# STM32F108CBT6.net
KiCad netlist of a schematic drawn in Altium Designer
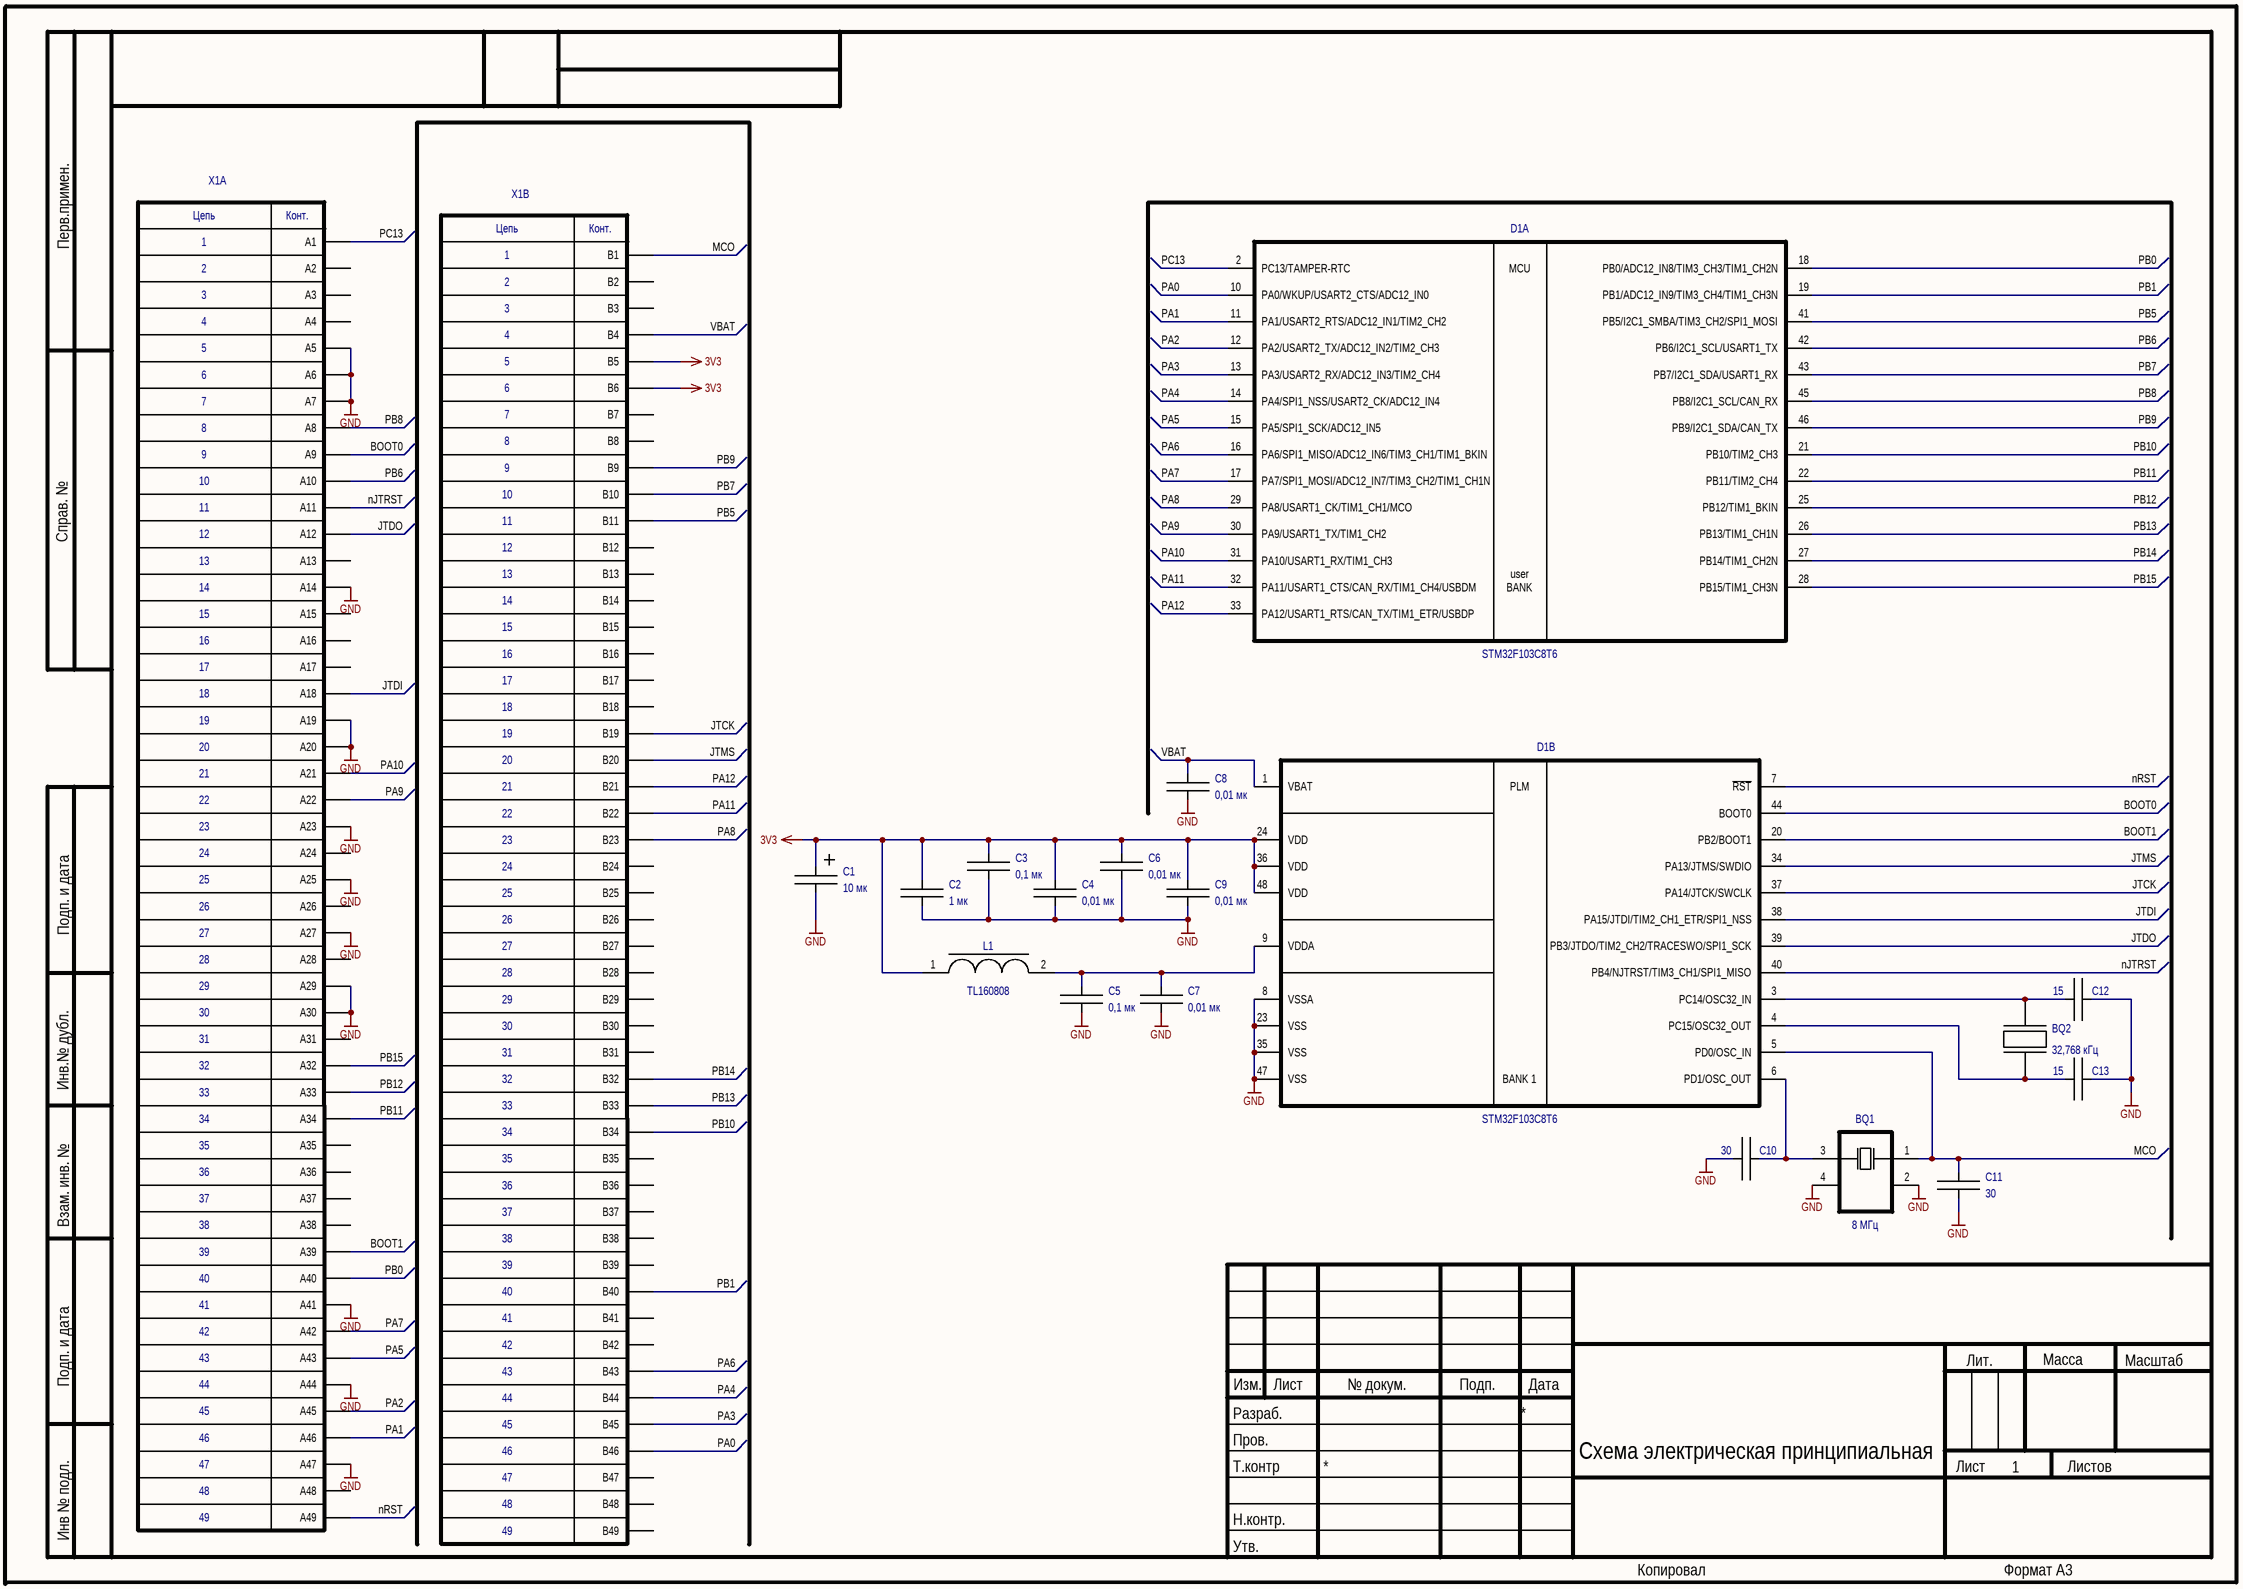
[diagram p0: Модуль STM32F108CBT6.SchDoc]

(export (version "E")
  (design (tool "Eeschema 10.0.6"))
  (components
    (comp (ref "BQ1")
      (value "8 МГц")
      (footprint "SMD3225_4P20MHZ20PF10PPM")
      (fields (field (name "PARTNUMBER") "MQ-12.000-18") (field (name "Comment") "кварцевый резонатор_1"))
      (libsource (lib "Lisaveta_SCH") (part "кварцевый резонатор_1"))
    )
    (comp (ref "BQ2")
      (value "32,768 кГц")
      (footprint "SMD3215_2P32768KHZ125PF10PPM")
      (fields (field (name "PARTNUMBER") "32,768 кГц 3215 SMD") (field (name "Comment") "3215"))
      (libsource (lib "Lisaveta") (part "кварцевый резонатор"))
    )
    (comp (ref "C1")
      (value "10 мк")
      (footprint "K53-68_3216(A)")
      (fields (field (name "Comment") "A-case"))
      (libsource (lib "Lisaveta_SCH") (part "C+"))
    )
    (comp (ref "C2")
      (value "1 мк")
      (footprint "K10-69B_2.0_1.25(0805)")
      (fields (field (name "Comment") "0805"))
      (libsource (lib "Lisaveta") (part "C"))
    )
    (comp (ref "C3")
      (value "0,1 мк")
      (footprint "K10-79_1.6_0.8(0603)")
      (fields (field (name "Comment") "0603"))
      (libsource (lib "Lisaveta") (part "C"))
    )
    (comp (ref "C4")
      (value "0,01 мк")
      (footprint "K10-79_1.6_0.8(0603)")
      (fields (field (name "Comment") "0603"))
      (libsource (lib "Lisaveta") (part "C"))
    )
    (comp (ref "C5")
      (value "0,1 мк")
      (footprint "K10-79_1.6_0.8(0603)")
      (fields (field (name "Comment") "0603"))
      (libsource (lib "Lisaveta") (part "C"))
    )
    (comp (ref "C6")
      (value "0,01 мк")
      (footprint "K10-79_1.6_0.8(0603)")
      (fields (field (name "Comment") "0603"))
      (libsource (lib "Lisaveta") (part "C"))
    )
    (comp (ref "C7")
      (value "0,01 мк")
      (footprint "K10-79_1.6_0.8(0603)")
      (fields (field (name "Comment") "0603"))
      (libsource (lib "Lisaveta") (part "C"))
    )
    (comp (ref "C8")
      (value "0,01 мк")
      (footprint "K10-79_1.6_0.8(0603)")
      (fields (field (name "Comment") "0603"))
      (libsource (lib "Lisaveta") (part "C"))
    )
    (comp (ref "C9")
      (value "0,01 мк")
      (footprint "K10-79_1.6_0.8(0603)")
      (fields (field (name "Comment") "0603"))
      (libsource (lib "Lisaveta") (part "C"))
    )
    (comp (ref "C10")
      (value "30")
      (footprint "K10-79_1.6_0.8(0603)")
      (fields (field (name "Comment") "0603"))
      (libsource (lib "Lisaveta") (part "C"))
    )
    (comp (ref "C11")
      (value "30")
      (footprint "K10-79_1.6_0.8(0603)")
      (fields (field (name "Comment") "0603"))
      (libsource (lib "Lisaveta") (part "C"))
    )
    (comp (ref "C12")
      (value "15")
      (footprint "K10-79_1.6_0.8(0603)")
      (fields (field (name "Comment") "0603"))
      (libsource (lib "Lisaveta") (part "C"))
    )
    (comp (ref "C13")
      (value "15")
      (footprint "K10-79_1.6_0.8(0603)")
      (fields (field (name "Comment") "0603"))
      (libsource (lib "Lisaveta") (part "C"))
    )
    (comp (ref "D1")
      (value "STM32F103C8T6")
      (footprint "LQFP48")
      (fields (field (name "Comment") " (LQFP-48) Xilinx"))
      (libsource (lib "Lisaveta_SCH") (part "stm32f103c8t6"))
    )
    (comp (ref "L1")
      (value "TL160808")
      (footprint "742792651")
      (fields (field (name "Comment") "0603"))
      (libsource (lib "Lisaveta") (part "SH6028-5R0YLB"))
    )
    (comp (ref "X1")
      (value "KONT_POLE_MEZ")
      (footprint "3113-112t_otv")
      (libsource (lib "Lisaveta_SCH") (part "3113-112T"))
    )
  )
  (nets
    (net (code "1") (name "/BOOT0") (class "Default")
      (node (ref "D1") (pin "44") (pinfunction "BOOT0_44") (pintype "passive"))
      (node (ref "X1") (pin "A9") (pinfunction "A9_A9") (pintype "passive"))
    )
    (net (code "2") (name "/BOOT1") (class "Default")
      (node (ref "D1") (pin "20") (pinfunction "PB2/BOOT1_20") (pintype "passive"))
      (node (ref "X1") (pin "A39") (pinfunction "A39_A39") (pintype "passive"))
    )
    (net (code "3") (name "/JTCK") (class "Default")
      (node (ref "D1") (pin "37") (pinfunction "PA14/JTCK/SWCLK_37") (pintype "passive"))
      (node (ref "X1") (pin "B19") (pinfunction "B19_B19") (pintype "passive"))
    )
    (net (code "4") (name "/JTDI") (class "Default")
      (node (ref "D1") (pin "38") (pinfunction "PA15/JTDI/TIM2_CH1_ETR/SPI1_NSS_38") (pintype "passive"))
      (node (ref "X1") (pin "A18") (pinfunction "A18_A18") (pintype "passive"))
    )
    (net (code "5") (name "/JTDO") (class "Default")
      (node (ref "D1") (pin "39") (pinfunction "PB3/JTDO/TIM2_CH2/TRACESWO/SPI1_SCK_39") (pintype "passive"))
      (node (ref "X1") (pin "A12") (pinfunction "A12_A12") (pintype "passive"))
    )
    (net (code "6") (name "/JTMS") (class "Default")
      (node (ref "D1") (pin "34") (pinfunction "PA13/JTMS/SWDIO_34") (pintype "passive"))
      (node (ref "X1") (pin "B20") (pinfunction "B20_B20") (pintype "passive"))
    )
    (net (code "7") (name "/MCO") (class "Default")
      (node (ref "BQ1") (pin "1") (pinfunction "1_1") (pintype "passive"))
      (node (ref "C11") (pin "2") (pinfunction "2_2") (pintype "passive"))
      (node (ref "D1") (pin "5") (pinfunction "PD0/OSC_IN_5") (pintype "passive"))
      (node (ref "X1") (pin "B1") (pinfunction "B1_B1") (pintype "passive"))
    )
    (net (code "8") (name "/PA0") (class "Default")
      (node (ref "D1") (pin "10") (pinfunction "PA0/WKUP/USART2_CTS/ADC12_IN0_10") (pintype "passive"))
      (node (ref "X1") (pin "B46") (pinfunction "B46_B46") (pintype "passive"))
    )
    (net (code "9") (name "/PA1") (class "Default")
      (node (ref "D1") (pin "11") (pinfunction "PA1/USART2_RTS/ADC12_IN1/TIM2_CH2_11") (pintype "passive"))
      (node (ref "X1") (pin "A46") (pinfunction "A46_A46") (pintype "passive"))
    )
    (net (code "10") (name "/PA2") (class "Default")
      (node (ref "D1") (pin "12") (pinfunction "PA2/USART2_TX/ADC12_IN2/TIM2_CH3_12") (pintype "passive"))
      (node (ref "X1") (pin "A45") (pinfunction "A45_A45") (pintype "passive"))
    )
    (net (code "11") (name "/PA3") (class "Default")
      (node (ref "D1") (pin "13") (pinfunction "PA3/USART2_RX/ADC12_IN3/TIM2_CH4_13") (pintype "passive"))
      (node (ref "X1") (pin "B45") (pinfunction "B45_B45") (pintype "passive"))
    )
    (net (code "12") (name "/PA4") (class "Default")
      (node (ref "D1") (pin "14") (pinfunction "PA4/SPI1_NSS/USART2_CK/ADC12_IN4_14") (pintype "passive"))
      (node (ref "X1") (pin "B44") (pinfunction "B44_B44") (pintype "passive"))
    )
    (net (code "13") (name "/PA5") (class "Default")
      (node (ref "D1") (pin "15") (pinfunction "PA5/SPI1_SCK/ADC12_IN5_15") (pintype "passive"))
      (node (ref "X1") (pin "A43") (pinfunction "A43_A43") (pintype "passive"))
    )
    (net (code "14") (name "/PA6") (class "Default")
      (node (ref "D1") (pin "16") (pinfunction "PA6/SPI1_MISO/ADC12_IN6/TIM3_CH1/TIM1_BKIN_16") (pintype "passive"))
      (node (ref "X1") (pin "B43") (pinfunction "B43_B43") (pintype "passive"))
    )
    (net (code "15") (name "/PA7") (class "Default")
      (node (ref "D1") (pin "17") (pinfunction "PA7/SPI1_MOSI/ADC12_IN7/TIM3_CH2/TIM1_CH1N_17") (pintype "passive"))
      (node (ref "X1") (pin "A42") (pinfunction "A42_A42") (pintype "passive"))
    )
    (net (code "16") (name "/PA8") (class "Default")
      (node (ref "D1") (pin "29") (pinfunction "PA8/USART1_CK/TIM1_CH1/MCO_29") (pintype "passive"))
      (node (ref "X1") (pin "B23") (pinfunction "B23_B23") (pintype "passive"))
    )
    (net (code "17") (name "/PA9") (class "Default")
      (node (ref "D1") (pin "30") (pinfunction "PA9/USART1_TX/TIM1_CH2_30") (pintype "passive"))
      (node (ref "X1") (pin "A22") (pinfunction "A22_A22") (pintype "passive"))
    )
    (net (code "18") (name "/PA10") (class "Default")
      (node (ref "D1") (pin "31") (pinfunction "PA10/USART1_RX/TIM1_CH3_31") (pintype "passive"))
      (node (ref "X1") (pin "A21") (pinfunction "A21_A21") (pintype "passive"))
    )
    (net (code "19") (name "/PA11") (class "Default")
      (node (ref "D1") (pin "32") (pinfunction "PA11/USART1_CTS/CAN_RX/TIM1_CH4/USBDM_32") (pintype "passive"))
      (node (ref "X1") (pin "B22") (pinfunction "B22_B22") (pintype "passive"))
    )
    (net (code "20") (name "/PA12") (class "Default")
      (node (ref "D1") (pin "33") (pinfunction "PA12/USART1_RTS/CAN_TX/TIM1_ETR/USBDP_33") (pintype "passive"))
      (node (ref "X1") (pin "B21") (pinfunction "B21_B21") (pintype "passive"))
    )
    (net (code "21") (name "/PB0") (class "Default")
      (node (ref "D1") (pin "18") (pinfunction "PB0/ADC12_IN8/TIM3_CH3/TIM1_CH2N_18") (pintype "passive"))
      (node (ref "X1") (pin "A40") (pinfunction "A40_A40") (pintype "passive"))
    )
    (net (code "22") (name "/PB1") (class "Default")
      (node (ref "D1") (pin "19") (pinfunction "PB1/ADC12_IN9/TIM3_CH4/TIM1_CH3N_19") (pintype "passive"))
      (node (ref "X1") (pin "B40") (pinfunction "B40_B40") (pintype "passive"))
    )
    (net (code "23") (name "/PB5") (class "Default")
      (node (ref "D1") (pin "41") (pinfunction "PB5/I2C1_SMBA/TIM3_CH2/SPI1_MOSI_41") (pintype "passive"))
      (node (ref "X1") (pin "B11") (pinfunction "B11_B11") (pintype "passive"))
    )
    (net (code "24") (name "/PB6") (class "Default")
      (node (ref "D1") (pin "42") (pinfunction "PB6/I2C1_SCL/USART1_TX_42") (pintype "passive"))
      (node (ref "X1") (pin "A10") (pinfunction "A10_A10") (pintype "passive"))
    )
    (net (code "25") (name "/PB7") (class "Default")
      (node (ref "D1") (pin "43") (pinfunction "PB7/I2C1_SDA/USART1_RX_43") (pintype "passive"))
      (node (ref "X1") (pin "B10") (pinfunction "B10_B10") (pintype "passive"))
    )
    (net (code "26") (name "/PB8") (class "Default")
      (node (ref "D1") (pin "45") (pinfunction "PB8/I2C1_SCL/CAN_RX_45") (pintype "passive"))
      (node (ref "X1") (pin "A8") (pinfunction "A8_A8") (pintype "passive"))
    )
    (net (code "27") (name "/PB9") (class "Default")
      (node (ref "D1") (pin "46") (pinfunction "PB9/I2C1_SDA/CAN_TX_46") (pintype "passive"))
      (node (ref "X1") (pin "B9") (pinfunction "B9_B9") (pintype "passive"))
    )
    (net (code "28") (name "/PB10") (class "Default")
      (node (ref "D1") (pin "21") (pinfunction "PB10/TIM2_CH3_21") (pintype "passive"))
      (node (ref "X1") (pin "B34") (pinfunction "B34_B34") (pintype "passive"))
    )
    (net (code "29") (name "/PB11") (class "Default")
      (node (ref "D1") (pin "22") (pinfunction "PB11/TIM2_CH4_22") (pintype "passive"))
      (node (ref "X1") (pin "A34") (pinfunction "A34_A34") (pintype "passive"))
    )
    (net (code "30") (name "/PB12") (class "Default")
      (node (ref "D1") (pin "25") (pinfunction "PB12/TIM1_BKIN_25") (pintype "passive"))
      (node (ref "X1") (pin "A33") (pinfunction "A33_A33") (pintype "passive"))
    )
    (net (code "31") (name "/PB13") (class "Default")
      (node (ref "D1") (pin "26") (pinfunction "PB13/TIM1_CH1N_26") (pintype "passive"))
      (node (ref "X1") (pin "B33") (pinfunction "B33_B33") (pintype "passive"))
    )
    (net (code "32") (name "/PB14") (class "Default")
      (node (ref "D1") (pin "27") (pinfunction "PB14/TIM1_CH2N_27") (pintype "passive"))
      (node (ref "X1") (pin "B32") (pinfunction "B32_B32") (pintype "passive"))
    )
    (net (code "33") (name "/PB15") (class "Default")
      (node (ref "D1") (pin "28") (pinfunction "PB15/TIM1_CH3N_28") (pintype "passive"))
      (node (ref "X1") (pin "A32") (pinfunction "A32_A32") (pintype "passive"))
    )
    (net (code "34") (name "/PC13") (class "Default")
      (node (ref "D1") (pin "2") (pinfunction "PC13/TAMPER-RTC_2") (pintype "passive"))
      (node (ref "X1") (pin "A1") (pinfunction "A1_A1") (pintype "passive"))
    )
    (net (code "35") (name "/VBAT") (class "Default")
      (node (ref "C8") (pin "2") (pinfunction "2_2") (pintype "passive"))
      (node (ref "D1") (pin "1") (pinfunction "VBAT_1") (pintype "passive"))
      (node (ref "X1") (pin "B4") (pinfunction "B4_B4") (pintype "passive"))
    )
    (net (code "36") (name "/nJTRST") (class "Default")
      (node (ref "D1") (pin "40") (pinfunction "PB4/NJTRST/TIM3_CH1/SPI1_MISO_40") (pintype "passive"))
      (node (ref "X1") (pin "A11") (pinfunction "A11_A11") (pintype "passive"))
    )
    (net (code "37") (name "/nRST") (class "Default")
      (node (ref "D1") (pin "7") (pinfunction "~{RST}_7") (pintype "passive"))
      (node (ref "X1") (pin "A49") (pinfunction "A49_A49") (pintype "passive"))
    )
    (net (code "38") (name "3V3") (class "Default")
      (node (ref "C1") (pin "1") (pinfunction "1_1") (pintype "passive"))
      (node (ref "C2") (pin "2") (pinfunction "2_2") (pintype "passive"))
      (node (ref "C3") (pin "2") (pinfunction "2_2") (pintype "passive"))
      (node (ref "C4") (pin "2") (pinfunction "2_2") (pintype "passive"))
      (node (ref "C6") (pin "2") (pinfunction "2_2") (pintype "passive"))
      (node (ref "C9") (pin "2") (pinfunction "2_2") (pintype "passive"))
      (node (ref "D1") (pin "24") (pinfunction "VDD_24") (pintype "passive"))
      (node (ref "D1") (pin "36") (pinfunction "VDD_36") (pintype "passive"))
      (node (ref "D1") (pin "48") (pinfunction "VDD_48") (pintype "passive"))
      (node (ref "L1") (pin "1") (pinfunction "1_1") (pintype "passive"))
      (node (ref "X1") (pin "B5") (pinfunction "B5_B5") (pintype "passive"))
      (node (ref "X1") (pin "B6") (pinfunction "B6_B6") (pintype "passive"))
    )
    (net (code "39") (name "GND") (class "Default")
      (node (ref "BQ1") (pin "2") (pinfunction "GND_2") (pintype "passive"))
      (node (ref "BQ1") (pin "4") (pinfunction "GND_4") (pintype "passive"))
      (node (ref "C1") (pin "2") (pinfunction "2_2") (pintype "passive"))
      (node (ref "C10") (pin "1") (pinfunction "1_1") (pintype "passive"))
      (node (ref "C11") (pin "1") (pinfunction "1_1") (pintype "passive"))
      (node (ref "C12") (pin "1") (pinfunction "1_1") (pintype "passive"))
      (node (ref "C13") (pin "1") (pinfunction "1_1") (pintype "passive"))
      (node (ref "C2") (pin "1") (pinfunction "1_1") (pintype "passive"))
      (node (ref "C3") (pin "1") (pinfunction "1_1") (pintype "passive"))
      (node (ref "C4") (pin "1") (pinfunction "1_1") (pintype "passive"))
      (node (ref "C5") (pin "1") (pinfunction "1_1") (pintype "passive"))
      (node (ref "C6") (pin "1") (pinfunction "1_1") (pintype "passive"))
      (node (ref "C7") (pin "1") (pinfunction "1_1") (pintype "passive"))
      (node (ref "C8") (pin "1") (pinfunction "1_1") (pintype "passive"))
      (node (ref "C9") (pin "1") (pinfunction "1_1") (pintype "passive"))
      (node (ref "D1") (pin "23") (pinfunction "VSS_23") (pintype "passive"))
      (node (ref "D1") (pin "35") (pinfunction "VSS_35") (pintype "passive"))
      (node (ref "D1") (pin "47") (pinfunction "VSS_47") (pintype "passive"))
      (node (ref "D1") (pin "8") (pinfunction "VSSA_8") (pintype "passive"))
      (node (ref "X1") (pin "A14") (pinfunction "A14_A14") (pintype "passive"))
      (node (ref "X1") (pin "A19") (pinfunction "A19_A19") (pintype "passive"))
      (node (ref "X1") (pin "A20") (pinfunction "A20_A20") (pintype "passive"))
      (node (ref "X1") (pin "A23") (pinfunction "A23_A23") (pintype "passive"))
      (node (ref "X1") (pin "A25") (pinfunction "A25_A25") (pintype "passive"))
      (node (ref "X1") (pin "A27") (pinfunction "A27_A27") (pintype "passive"))
      (node (ref "X1") (pin "A29") (pinfunction "A29_A29") (pintype "passive"))
      (node (ref "X1") (pin "A30") (pinfunction "A30_A30") (pintype "passive"))
      (node (ref "X1") (pin "A41") (pinfunction "A41_A41") (pintype "passive"))
      (node (ref "X1") (pin "A44") (pinfunction "A44_A44") (pintype "passive"))
      (node (ref "X1") (pin "A47") (pinfunction "A47_A47") (pintype "passive"))
      (node (ref "X1") (pin "A5") (pinfunction "A5_A5") (pintype "passive"))
      (node (ref "X1") (pin "A6") (pinfunction "A6_A6") (pintype "passive"))
      (node (ref "X1") (pin "A7") (pinfunction "A7_A7") (pintype "passive"))
    )
    (net (code "40") (name "Net-(BQ2-GND)") (class "Default")
      (node (ref "BQ2") (pin "2") (pinfunction "GND_2") (pintype "passive"))
      (node (ref "C13") (pin "2") (pinfunction "2_2") (pintype "passive"))
      (node (ref "D1") (pin "4") (pinfunction "PC15/OSC32_OUT_4") (pintype "passive"))
    )
    (net (code "41") (name "Net-(BQ2-IN)") (class "Default")
      (node (ref "BQ2") (pin "1") (pinfunction "IN_1") (pintype "passive"))
      (node (ref "C12") (pin "2") (pinfunction "2_2") (pintype "passive"))
      (node (ref "D1") (pin "3") (pinfunction "PC14/OSC32_IN_3") (pintype "passive"))
    )
    (net (code "42") (name "Net-(D1B-PD1{slash}OSC_OUT)") (class "Default")
      (node (ref "BQ1") (pin "3") (pinfunction "3_3") (pintype "passive"))
      (node (ref "C10") (pin "2") (pinfunction "2_2") (pintype "passive"))
      (node (ref "D1") (pin "6") (pinfunction "PD1/OSC_OUT_6") (pintype "passive"))
    )
    (net (code "43") (name "Net-(D1B-VDDA)") (class "Default")
      (node (ref "C5") (pin "2") (pinfunction "2_2") (pintype "passive"))
      (node (ref "C7") (pin "2") (pinfunction "2_2") (pintype "passive"))
      (node (ref "D1") (pin "9") (pinfunction "VDDA_9") (pintype "passive"))
      (node (ref "L1") (pin "2") (pinfunction "2_2") (pintype "passive"))
    )
    (net (code "44") (name "unconnected-(X1-PadA2)") (class "Default")
      (node (ref "X1") (pin "A2") (pinfunction "A2_A2") (pintype "passive"))
    )
    (net (code "45") (name "unconnected-(X1-PadA3)") (class "Default")
      (node (ref "X1") (pin "A3") (pinfunction "A3_A3") (pintype "passive"))
    )
    (net (code "46") (name "unconnected-(X1-PadA4)") (class "Default")
      (node (ref "X1") (pin "A4") (pinfunction "A4_A4") (pintype "passive"))
    )
    (net (code "47") (name "unconnected-(X1-PadA13)") (class "Default")
      (node (ref "X1") (pin "A13") (pinfunction "A13_A13") (pintype "passive"))
    )
    (net (code "48") (name "unconnected-(X1-PadA15)") (class "Default")
      (node (ref "X1") (pin "A15") (pinfunction "A15_A15") (pintype "passive"))
    )
    (net (code "49") (name "unconnected-(X1-PadA16)") (class "Default")
      (node (ref "X1") (pin "A16") (pinfunction "A16_A16") (pintype "passive"))
    )
    (net (code "50") (name "unconnected-(X1-PadA17)") (class "Default")
      (node (ref "X1") (pin "A17") (pinfunction "A17_A17") (pintype "passive"))
    )
    (net (code "51") (name "unconnected-(X1-PadA24)") (class "Default")
      (node (ref "X1") (pin "A24") (pinfunction "A24_A24") (pintype "passive"))
    )
    (net (code "52") (name "unconnected-(X1-PadA26)") (class "Default")
      (node (ref "X1") (pin "A26") (pinfunction "A26_A26") (pintype "passive"))
    )
    (net (code "53") (name "unconnected-(X1-PadA28)") (class "Default")
      (node (ref "X1") (pin "A28") (pinfunction "A28_A28") (pintype "passive"))
    )
    (net (code "54") (name "unconnected-(X1-PadA31)") (class "Default")
      (node (ref "X1") (pin "A31") (pinfunction "A31_A31") (pintype "passive"))
    )
    (net (code "55") (name "unconnected-(X1-PadA35)") (class "Default")
      (node (ref "X1") (pin "A35") (pinfunction "A35_A35") (pintype "passive"))
    )
    (net (code "56") (name "unconnected-(X1-PadA36)") (class "Default")
      (node (ref "X1") (pin "A36") (pinfunction "A36_A36") (pintype "passive"))
    )
    (net (code "57") (name "unconnected-(X1-PadA37)") (class "Default")
      (node (ref "X1") (pin "A37") (pinfunction "A37_A37") (pintype "passive"))
    )
    (net (code "58") (name "unconnected-(X1-PadA38)") (class "Default")
      (node (ref "X1") (pin "A38") (pinfunction "A38_A38") (pintype "passive"))
    )
    (net (code "59") (name "unconnected-(X1-PadA48)") (class "Default")
      (node (ref "X1") (pin "A48") (pinfunction "A48_A48") (pintype "passive"))
    )
    (net (code "60") (name "unconnected-(X1-PadB2)") (class "Default")
      (node (ref "X1") (pin "B2") (pinfunction "B2_B2") (pintype "passive"))
    )
    (net (code "61") (name "unconnected-(X1-PadB3)") (class "Default")
      (node (ref "X1") (pin "B3") (pinfunction "B3_B3") (pintype "passive"))
    )
    (net (code "62") (name "unconnected-(X1-PadB7)") (class "Default")
      (node (ref "X1") (pin "B7") (pinfunction "B7_B7") (pintype "passive"))
    )
    (net (code "63") (name "unconnected-(X1-PadB8)") (class "Default")
      (node (ref "X1") (pin "B8") (pinfunction "B8_B8") (pintype "passive"))
    )
    (net (code "64") (name "unconnected-(X1-PadB12)") (class "Default")
      (node (ref "X1") (pin "B12") (pinfunction "B12_B12") (pintype "passive"))
    )
    (net (code "65") (name "unconnected-(X1-PadB13)") (class "Default")
      (node (ref "X1") (pin "B13") (pinfunction "B13_B13") (pintype "passive"))
    )
    (net (code "66") (name "unconnected-(X1-PadB14)") (class "Default")
      (node (ref "X1") (pin "B14") (pinfunction "B14_B14") (pintype "passive"))
    )
    (net (code "67") (name "unconnected-(X1-PadB15)") (class "Default")
      (node (ref "X1") (pin "B15") (pinfunction "B15_B15") (pintype "passive"))
    )
    (net (code "68") (name "unconnected-(X1-PadB16)") (class "Default")
      (node (ref "X1") (pin "B16") (pinfunction "B16_B16") (pintype "passive"))
    )
    (net (code "69") (name "unconnected-(X1-PadB17)") (class "Default")
      (node (ref "X1") (pin "B17") (pinfunction "B17_B17") (pintype "passive"))
    )
    (net (code "70") (name "unconnected-(X1-PadB18)") (class "Default")
      (node (ref "X1") (pin "B18") (pinfunction "B18_B18") (pintype "passive"))
    )
    (net (code "71") (name "unconnected-(X1-PadB24)") (class "Default")
      (node (ref "X1") (pin "B24") (pinfunction "B24_B24") (pintype "passive"))
    )
    (net (code "72") (name "unconnected-(X1-PadB25)") (class "Default")
      (node (ref "X1") (pin "B25") (pinfunction "B25_B25") (pintype "passive"))
    )
    (net (code "73") (name "unconnected-(X1-PadB26)") (class "Default")
      (node (ref "X1") (pin "B26") (pinfunction "B26_B26") (pintype "passive"))
    )
    (net (code "74") (name "unconnected-(X1-PadB27)") (class "Default")
      (node (ref "X1") (pin "B27") (pinfunction "B27_B27") (pintype "passive"))
    )
    (net (code "75") (name "unconnected-(X1-PadB28)") (class "Default")
      (node (ref "X1") (pin "B28") (pinfunction "B28_B28") (pintype "passive"))
    )
    (net (code "76") (name "unconnected-(X1-PadB29)") (class "Default")
      (node (ref "X1") (pin "B29") (pinfunction "B29_B29") (pintype "passive"))
    )
    (net (code "77") (name "unconnected-(X1-PadB30)") (class "Default")
      (node (ref "X1") (pin "B30") (pinfunction "B30_B30") (pintype "passive"))
    )
    (net (code "78") (name "unconnected-(X1-PadB31)") (class "Default")
      (node (ref "X1") (pin "B31") (pinfunction "B31_B31") (pintype "passive"))
    )
    (net (code "79") (name "unconnected-(X1-PadB35)") (class "Default")
      (node (ref "X1") (pin "B35") (pinfunction "B35_B35") (pintype "passive"))
    )
    (net (code "80") (name "unconnected-(X1-PadB36)") (class "Default")
      (node (ref "X1") (pin "B36") (pinfunction "B36_B36") (pintype "passive"))
    )
    (net (code "81") (name "unconnected-(X1-PadB37)") (class "Default")
      (node (ref "X1") (pin "B37") (pinfunction "B37_B37") (pintype "passive"))
    )
    (net (code "82") (name "unconnected-(X1-PadB38)") (class "Default")
      (node (ref "X1") (pin "B38") (pinfunction "B38_B38") (pintype "passive"))
    )
    (net (code "83") (name "unconnected-(X1-PadB39)") (class "Default")
      (node (ref "X1") (pin "B39") (pinfunction "B39_B39") (pintype "passive"))
    )
    (net (code "84") (name "unconnected-(X1-PadB41)") (class "Default")
      (node (ref "X1") (pin "B41") (pinfunction "B41_B41") (pintype "passive"))
    )
    (net (code "85") (name "unconnected-(X1-PadB42)") (class "Default")
      (node (ref "X1") (pin "B42") (pinfunction "B42_B42") (pintype "passive"))
    )
    (net (code "86") (name "unconnected-(X1-PadB47)") (class "Default")
      (node (ref "X1") (pin "B47") (pinfunction "B47_B47") (pintype "passive"))
    )
    (net (code "87") (name "unconnected-(X1-PadB48)") (class "Default")
      (node (ref "X1") (pin "B48") (pinfunction "B48_B48") (pintype "passive"))
    )
    (net (code "88") (name "unconnected-(X1-PadB49)") (class "Default")
      (node (ref "X1") (pin "B49") (pinfunction "B49_B49") (pintype "passive"))
    )
  )
)
